# SWNUI.net
KiCad netlist of a schematic drawn in EAGLE
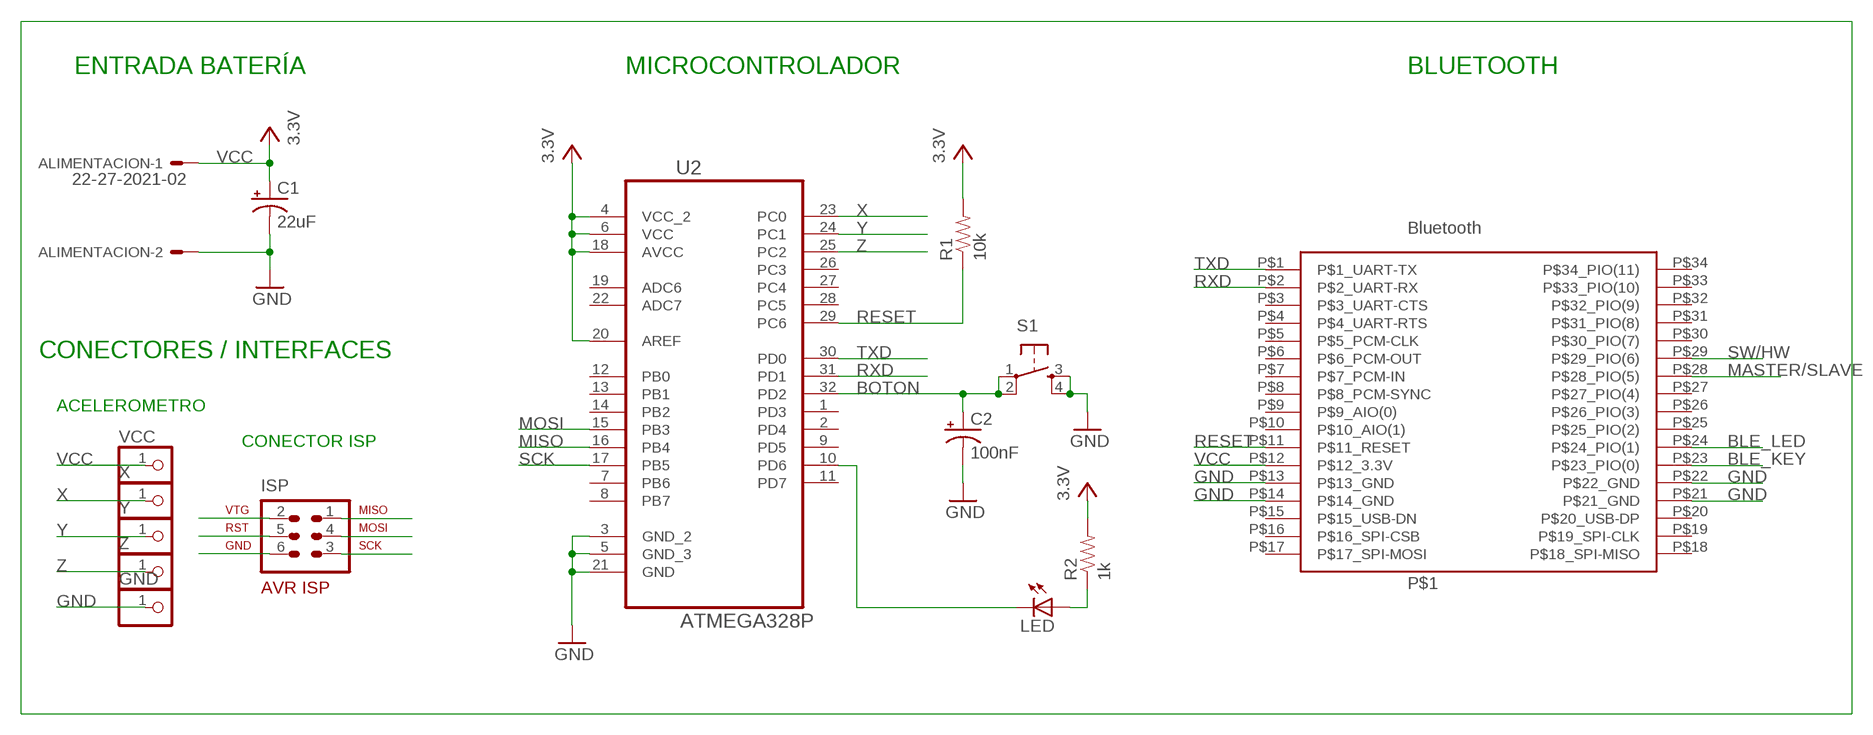
[diagram p0: schematic, sheet 1]

(export (version "E")
  (design (tool "Eeschema 10.0.6"))
  (components
    (comp (ref "ALIMENTACION")
      (value "22-27-2021-02")
      (footprint "eagle-import:6410-02")
      (libsource (lib "eagle-import") (part "22-?-0227-2021"))
    )
    (comp (ref "C1")
      (value "22uF")
      (footprint "eagle-import:EIA3216")
      (libsource (lib "eagle-import") (part "CAP_POL1206"))
    )
    (comp (ref "C2")
      (value "100nF")
      (footprint "eagle-import:EIA3216")
      (libsource (lib "eagle-import") (part "CAP_POL1206"))
    )
    (comp (ref "GND")
      (value "PINHD-1X1")
      (footprint "eagle-import:1X01")
      (libsource (lib "eagle-import") (part "PINHD-1X1"))
    )
    (comp (ref "ISP")
      (value "AVR-ISP-6")
      (footprint "eagle-import:AVR-ISP-6")
      (libsource (lib "eagle-import") (part "AVR-ISP-6"))
    )
    (comp (ref "LED")
      (value "LEDCHIP-LED0805")
      (footprint "eagle-import:CHIP-LED0805")
      (libsource (lib "eagle-import") (part "LEDCHIP-LED0805"))
    )
    (comp (ref "P$1")
      (value "Bluetooth")
      (footprint "eagle-import:BTM400")
      (libsource (lib "eagle-import") (part "BTM400-6B"))
    )
    (comp (ref "R1")
      (value "10k")
      (footprint "eagle-import:0805")
      (libsource (lib "eagle-import") (part "0.3OHM-1/8W-1%(0805)"))
    )
    (comp (ref "R2")
      (value "1k")
      (footprint "eagle-import:0805")
      (libsource (lib "eagle-import") (part "0.3OHM-1/8W-1%(0805)"))
    )
    (comp (ref "S1")
      (value "TAC_SWITCHPTH")
      (footprint "eagle-import:TACTILE-PTH")
      (libsource (lib "eagle-import") (part "TAC_SWITCHPTH"))
    )
    (comp (ref "U2")
      (value "ATMEGA328P")
      (footprint "eagle-import:QFP80P900X900X120-32N")
      (fields (field (name "MPN") "ATMEGA328P-AU"))
      (libsource (lib "eagle-import") (part "ATMEGA328P-AU"))
    )
    (comp (ref "VCC")
      (value "PINHD-1X1")
      (footprint "eagle-import:1X01")
      (libsource (lib "eagle-import") (part "PINHD-1X1"))
    )
    (comp (ref "X")
      (value "PINHD-1X1")
      (footprint "eagle-import:1X01")
      (libsource (lib "eagle-import") (part "PINHD-1X1"))
    )
    (comp (ref "Y")
      (value "PINHD-1X1")
      (footprint "eagle-import:1X01")
      (libsource (lib "eagle-import") (part "PINHD-1X1"))
    )
    (comp (ref "Z")
      (value "PINHD-1X1")
      (footprint "eagle-import:1X01")
      (libsource (lib "eagle-import") (part "PINHD-1X1"))
    )
  )
  (nets
    (net (code "1") (name "/BLE_KEY") (class "Default")
      (node (ref "P$1") (pin "P$23") (pinfunction "P$23_PIO(0)_P$23") (pintype "bidirectional"))
    )
    (net (code "2") (name "/BLE_LED") (class "Default")
      (node (ref "P$1") (pin "P$24") (pinfunction "P$24_PIO(1)_P$24") (pintype "bidirectional"))
    )
    (net (code "3") (name "/BOTON") (class "Default")
      (node (ref "C2") (pin "A") (pinfunction "+_A") (pintype "passive"))
      (node (ref "S1") (pin "1") (pinfunction "1_1") (pintype "passive"))
      (node (ref "S1") (pin "2") (pinfunction "2_2") (pintype "passive"))
      (node (ref "U2") (pin "32") (pinfunction "PD2_32") (pintype "bidirectional"))
    )
    (net (code "4") (name "/MASTER{slash}SLAVE") (class "Default")
      (node (ref "P$1") (pin "P$28") (pinfunction "P$28_PIO(5)_P$28") (pintype "bidirectional"))
    )
    (net (code "5") (name "/MISO") (class "Default")
      (node (ref "ISP") (pin "1") (pinfunction "1_1") (pintype "passive"))
      (node (ref "U2") (pin "16") (pinfunction "PB4_16") (pintype "bidirectional"))
    )
    (net (code "6") (name "/MOSI") (class "Default")
      (node (ref "ISP") (pin "4") (pinfunction "4_4") (pintype "passive"))
      (node (ref "U2") (pin "15") (pinfunction "PB3_15") (pintype "bidirectional"))
    )
    (net (code "7") (name "/RESET") (class "Default")
      (node (ref "ISP") (pin "5") (pinfunction "5_5") (pintype "passive"))
      (node (ref "P$1") (pin "P$11") (pinfunction "P$11_RESET_P$11") (pintype "input"))
      (node (ref "R1") (pin "1") (pinfunction "1_1") (pintype "passive"))
      (node (ref "U2") (pin "29") (pinfunction "PC6_29") (pintype "bidirectional"))
    )
    (net (code "8") (name "/RXD") (class "Default")
      (node (ref "P$1") (pin "P$2") (pinfunction "P$2_UART-RX_P$2") (pintype "input"))
      (node (ref "U2") (pin "31") (pinfunction "PD1_31") (pintype "bidirectional"))
    )
    (net (code "9") (name "/SCK") (class "Default")
      (node (ref "ISP") (pin "3") (pinfunction "3_3") (pintype "passive"))
      (node (ref "U2") (pin "17") (pinfunction "PB5_17") (pintype "bidirectional"))
    )
    (net (code "10") (name "/SW{slash}HW") (class "Default")
      (node (ref "P$1") (pin "P$29") (pinfunction "P$29_PIO(6)_P$29") (pintype "bidirectional"))
    )
    (net (code "11") (name "/TXD") (class "Default")
      (node (ref "P$1") (pin "P$1") (pinfunction "P$1_UART-TX_P$1") (pintype "output"))
      (node (ref "U2") (pin "30") (pinfunction "PD0_30") (pintype "bidirectional"))
    )
    (net (code "12") (name "/X") (class "Default")
      (node (ref "U2") (pin "23") (pinfunction "PC0_23") (pintype "bidirectional"))
      (node (ref "X") (pin "1") (pinfunction "1_1") (pintype "passive"))
    )
    (net (code "13") (name "/Y") (class "Default")
      (node (ref "U2") (pin "24") (pinfunction "PC1_24") (pintype "bidirectional"))
      (node (ref "Y") (pin "1") (pinfunction "1_1") (pintype "passive"))
    )
    (net (code "14") (name "/Z") (class "Default")
      (node (ref "U2") (pin "25") (pinfunction "PC2_25") (pintype "bidirectional"))
      (node (ref "Z") (pin "1") (pinfunction "1_1") (pintype "passive"))
    )
    (net (code "15") (name "3.3V") (class "Default")
      (node (ref "ALIMENTACION") (pin "1") (pinfunction "S_1") (pintype "passive"))
      (node (ref "C1") (pin "A") (pinfunction "+_A") (pintype "passive"))
      (node (ref "ISP") (pin "2") (pinfunction "2_2") (pintype "passive"))
      (node (ref "P$1") (pin "P$12") (pinfunction "P$12_3.3V_P$12") (pintype "power_in"))
      (node (ref "R1") (pin "2") (pinfunction "2_2") (pintype "passive"))
      (node (ref "R2") (pin "2") (pinfunction "2_2") (pintype "passive"))
      (node (ref "U2") (pin "18") (pinfunction "AVCC_18") (pintype "power_in"))
      (node (ref "U2") (pin "20") (pinfunction "AREF_20") (pintype "input"))
      (node (ref "U2") (pin "4") (pinfunction "VCC_2_4") (pintype "power_in"))
      (node (ref "U2") (pin "6") (pinfunction "VCC_6") (pintype "power_in"))
      (node (ref "VCC") (pin "1") (pinfunction "1_1") (pintype "passive"))
    )
    (net (code "16") (name "GND") (class "Default")
      (node (ref "ALIMENTACION") (pin "2") (pinfunction "S_2") (pintype "passive"))
      (node (ref "C1") (pin "C") (pinfunction "-_C") (pintype "passive"))
      (node (ref "C2") (pin "C") (pinfunction "-_C") (pintype "passive"))
      (node (ref "GND") (pin "1") (pinfunction "1_1") (pintype "passive"))
      (node (ref "ISP") (pin "6") (pinfunction "6_6") (pintype "passive"))
      (node (ref "P$1") (pin "P$13") (pinfunction "P$13_GND_P$13") (pintype "power_in"))
      (node (ref "P$1") (pin "P$14") (pinfunction "P$14_GND_P$14") (pintype "power_in"))
      (node (ref "P$1") (pin "P$21") (pinfunction "P$21_GND_P$21") (pintype "power_in"))
      (node (ref "P$1") (pin "P$22") (pinfunction "P$22_GND_P$22") (pintype "power_in"))
      (node (ref "S1") (pin "3") (pinfunction "3_3") (pintype "passive"))
      (node (ref "S1") (pin "4") (pinfunction "4_4") (pintype "passive"))
      (node (ref "U2") (pin "21") (pinfunction "GND_21") (pintype "passive"))
      (node (ref "U2") (pin "3") (pinfunction "GND_2_3") (pintype "passive"))
      (node (ref "U2") (pin "5") (pinfunction "GND_3_5") (pintype "passive"))
    )
    (net (code "17") (name "Net-(LED-PadA)") (class "Default")
      (node (ref "LED") (pin "A") (pinfunction "A_A") (pintype "passive"))
      (node (ref "R2") (pin "1") (pinfunction "1_1") (pintype "passive"))
    )
    (net (code "18") (name "Net-(U2-PD6)") (class "Default")
      (node (ref "LED") (pin "C") (pinfunction "C_C") (pintype "passive"))
      (node (ref "U2") (pin "10") (pinfunction "PD6_10") (pintype "bidirectional"))
    )
    (net (code "19") (name "unconnected-(P$1-P$3_UART-CTS-PadP$3)") (class "Default")
      (node (ref "P$1") (pin "P$3") (pinfunction "P$3_UART-CTS_P$3") (pintype "input"))
    )
    (net (code "20") (name "unconnected-(P$1-P$4_UART-RTS-PadP$4)") (class "Default")
      (node (ref "P$1") (pin "P$4") (pinfunction "P$4_UART-RTS_P$4") (pintype "output"))
    )
    (net (code "21") (name "unconnected-(P$1-P$5_PCM-CLK-PadP$5)") (class "Default")
      (node (ref "P$1") (pin "P$5") (pinfunction "P$5_PCM-CLK_P$5") (pintype "bidirectional"))
    )
    (net (code "22") (name "unconnected-(P$1-P$6_PCM-OUT-PadP$6)") (class "Default")
      (node (ref "P$1") (pin "P$6") (pinfunction "P$6_PCM-OUT_P$6") (pintype "output"))
    )
    (net (code "23") (name "unconnected-(P$1-P$7_PCM-IN-PadP$7)") (class "Default")
      (node (ref "P$1") (pin "P$7") (pinfunction "P$7_PCM-IN_P$7") (pintype "input"))
    )
    (net (code "24") (name "unconnected-(P$1-P$8_PCM-SYNC-PadP$8)") (class "Default")
      (node (ref "P$1") (pin "P$8") (pinfunction "P$8_PCM-SYNC_P$8") (pintype "bidirectional"))
    )
    (net (code "25") (name "unconnected-(P$1-P$9_AIO(0)-PadP$9)") (class "Default")
      (node (ref "P$1") (pin "P$9") (pinfunction "P$9_AIO(0)_P$9") (pintype "bidirectional"))
    )
    (net (code "26") (name "unconnected-(P$1-P$10_AIO(1)-PadP$10)") (class "Default")
      (node (ref "P$1") (pin "P$10") (pinfunction "P$10_AIO(1)_P$10") (pintype "bidirectional"))
    )
    (net (code "27") (name "unconnected-(P$1-P$15_USB-DN-PadP$15)") (class "Default")
      (node (ref "P$1") (pin "P$15") (pinfunction "P$15_USB-DN_P$15") (pintype "bidirectional"))
    )
    (net (code "28") (name "unconnected-(P$1-P$16_SPI-CSB-PadP$16)") (class "Default")
      (node (ref "P$1") (pin "P$16") (pinfunction "P$16_SPI-CSB_P$16") (pintype "input"))
    )
    (net (code "29") (name "unconnected-(P$1-P$17_SPI-MOSI-PadP$17)") (class "Default")
      (node (ref "P$1") (pin "P$17") (pinfunction "P$17_SPI-MOSI_P$17") (pintype "input"))
    )
    (net (code "30") (name "unconnected-(P$1-P$18_SPI-MISO-PadP$18)") (class "Default")
      (node (ref "P$1") (pin "P$18") (pinfunction "P$18_SPI-MISO_P$18") (pintype "output"))
    )
    (net (code "31") (name "unconnected-(P$1-P$19_SPI-CLK-PadP$19)") (class "Default")
      (node (ref "P$1") (pin "P$19") (pinfunction "P$19_SPI-CLK_P$19") (pintype "input"))
    )
    (net (code "32") (name "unconnected-(P$1-P$20_USB-DP-PadP$20)") (class "Default")
      (node (ref "P$1") (pin "P$20") (pinfunction "P$20_USB-DP_P$20") (pintype "bidirectional"))
    )
    (net (code "33") (name "unconnected-(P$1-P$25_PIO(2)-PadP$25)") (class "Default")
      (node (ref "P$1") (pin "P$25") (pinfunction "P$25_PIO(2)_P$25") (pintype "bidirectional"))
    )
    (net (code "34") (name "unconnected-(P$1-P$26_PIO(3)-PadP$26)") (class "Default")
      (node (ref "P$1") (pin "P$26") (pinfunction "P$26_PIO(3)_P$26") (pintype "bidirectional"))
    )
    (net (code "35") (name "unconnected-(P$1-P$27_PIO(4)-PadP$27)") (class "Default")
      (node (ref "P$1") (pin "P$27") (pinfunction "P$27_PIO(4)_P$27") (pintype "bidirectional"))
    )
    (net (code "36") (name "unconnected-(P$1-P$30_PIO(7)-PadP$30)") (class "Default")
      (node (ref "P$1") (pin "P$30") (pinfunction "P$30_PIO(7)_P$30") (pintype "bidirectional"))
    )
    (net (code "37") (name "unconnected-(P$1-P$31_PIO(8)-PadP$31)") (class "Default")
      (node (ref "P$1") (pin "P$31") (pinfunction "P$31_PIO(8)_P$31") (pintype "bidirectional"))
    )
    (net (code "38") (name "unconnected-(P$1-P$32_PIO(9)-PadP$32)") (class "Default")
      (node (ref "P$1") (pin "P$32") (pinfunction "P$32_PIO(9)_P$32") (pintype "bidirectional"))
    )
    (net (code "39") (name "unconnected-(P$1-P$33_PIO(10)-PadP$33)") (class "Default")
      (node (ref "P$1") (pin "P$33") (pinfunction "P$33_PIO(10)_P$33") (pintype "bidirectional"))
    )
    (net (code "40") (name "unconnected-(P$1-P$34_PIO(11)-PadP$34)") (class "Default")
      (node (ref "P$1") (pin "P$34") (pinfunction "P$34_PIO(11)_P$34") (pintype "bidirectional"))
    )
    (net (code "41") (name "unconnected-(U2-ADC6-Pad19)") (class "Default")
      (node (ref "U2") (pin "19") (pinfunction "ADC6_19") (pintype "input"))
    )
    (net (code "42") (name "unconnected-(U2-ADC7-Pad22)") (class "Default")
      (node (ref "U2") (pin "22") (pinfunction "ADC7_22") (pintype "input"))
    )
    (net (code "43") (name "unconnected-(U2-PB0-Pad12)") (class "Default")
      (node (ref "U2") (pin "12") (pinfunction "PB0_12") (pintype "bidirectional"))
    )
    (net (code "44") (name "unconnected-(U2-PB1-Pad13)") (class "Default")
      (node (ref "U2") (pin "13") (pinfunction "PB1_13") (pintype "bidirectional"))
    )
    (net (code "45") (name "unconnected-(U2-PB2-Pad14)") (class "Default")
      (node (ref "U2") (pin "14") (pinfunction "PB2_14") (pintype "bidirectional"))
    )
    (net (code "46") (name "unconnected-(U2-PB6-Pad7)") (class "Default")
      (node (ref "U2") (pin "7") (pinfunction "PB6_7") (pintype "bidirectional"))
    )
    (net (code "47") (name "unconnected-(U2-PB7-Pad8)") (class "Default")
      (node (ref "U2") (pin "8") (pinfunction "PB7_8") (pintype "bidirectional"))
    )
    (net (code "48") (name "unconnected-(U2-PC3-Pad26)") (class "Default")
      (node (ref "U2") (pin "26") (pinfunction "PC3_26") (pintype "bidirectional"))
    )
    (net (code "49") (name "unconnected-(U2-PC4-Pad27)") (class "Default")
      (node (ref "U2") (pin "27") (pinfunction "PC4_27") (pintype "bidirectional"))
    )
    (net (code "50") (name "unconnected-(U2-PC5-Pad28)") (class "Default")
      (node (ref "U2") (pin "28") (pinfunction "PC5_28") (pintype "bidirectional"))
    )
    (net (code "51") (name "unconnected-(U2-PD3-Pad1)") (class "Default")
      (node (ref "U2") (pin "1") (pinfunction "PD3_1") (pintype "bidirectional"))
    )
    (net (code "52") (name "unconnected-(U2-PD4-Pad2)") (class "Default")
      (node (ref "U2") (pin "2") (pinfunction "PD4_2") (pintype "bidirectional"))
    )
    (net (code "53") (name "unconnected-(U2-PD5-Pad9)") (class "Default")
      (node (ref "U2") (pin "9") (pinfunction "PD5_9") (pintype "bidirectional"))
    )
    (net (code "54") (name "unconnected-(U2-PD7-Pad11)") (class "Default")
      (node (ref "U2") (pin "11") (pinfunction "PD7_11") (pintype "bidirectional"))
    )
  )
)
